# CC-USB-CB.net
KiCad netlist of a schematic drawn in EAGLE
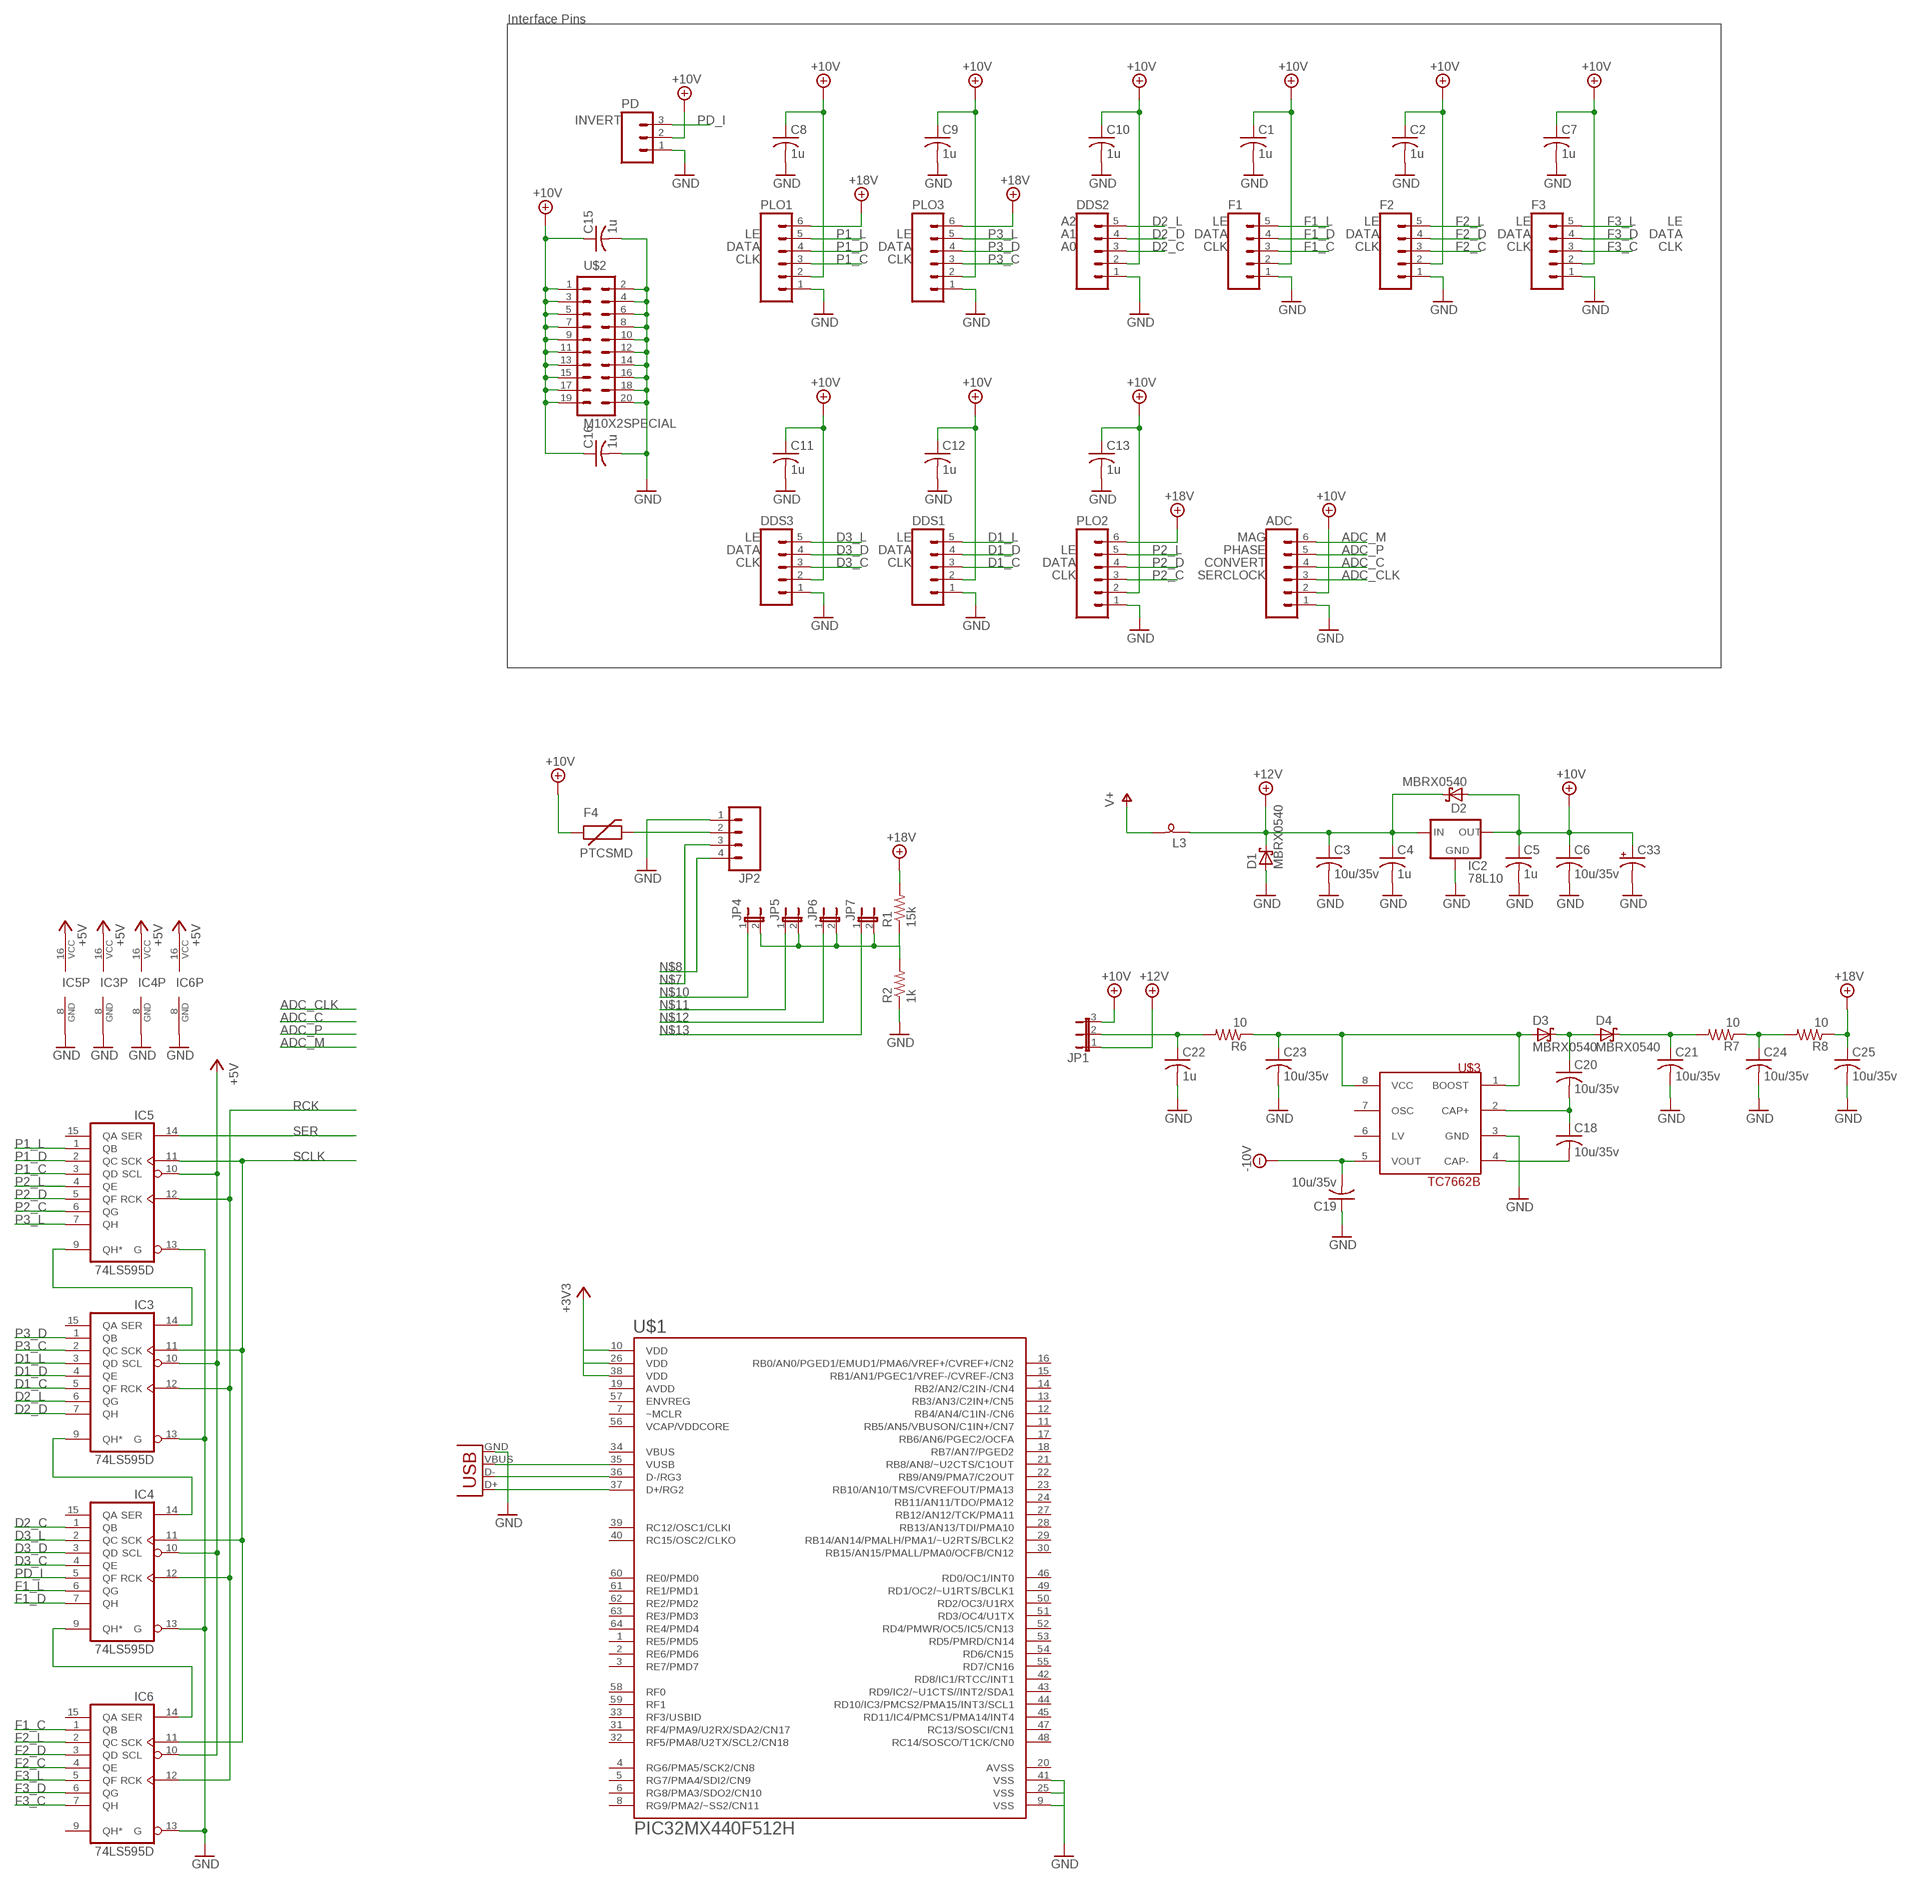
[diagram p0: schematic, sheet 1]

(export (version "E")
  (design (tool "Eeschema 10.0.6"))
  (components
    (comp (ref "ADC")
      (value "M06LOCK")
      (footprint "eagle-import:1X06_LOCK")
      (libsource (lib "eagle-import") (part "M06LOCK"))
    )
    (comp (ref "C1")
      (value "1u")
      (footprint "eagle-import:C0603")
      (libsource (lib "eagle-import") (part "C-USC0603"))
    )
    (comp (ref "C2")
      (value "1u")
      (footprint "eagle-import:C0603")
      (libsource (lib "eagle-import") (part "C-USC0603"))
    )
    (comp (ref "C3")
      (value "10u/35v")
      (footprint "eagle-import:C1206")
      (libsource (lib "eagle-import") (part "C-USC1206"))
    )
    (comp (ref "C4")
      (value "1u")
      (footprint "eagle-import:C0603")
      (libsource (lib "eagle-import") (part "C-USC0603"))
    )
    (comp (ref "C5")
      (value "1u")
      (footprint "eagle-import:C0603")
      (libsource (lib "eagle-import") (part "C-USC0603"))
    )
    (comp (ref "C6")
      (value "10u/35v")
      (footprint "eagle-import:C1206")
      (libsource (lib "eagle-import") (part "C-USC1206"))
    )
    (comp (ref "C7")
      (value "1u")
      (footprint "eagle-import:C0603")
      (libsource (lib "eagle-import") (part "C-USC0603"))
    )
    (comp (ref "C8")
      (value "1u")
      (footprint "eagle-import:C0603")
      (libsource (lib "eagle-import") (part "C-USC0603"))
    )
    (comp (ref "C9")
      (value "1u")
      (footprint "eagle-import:C0603")
      (libsource (lib "eagle-import") (part "C-USC0603"))
    )
    (comp (ref "C10")
      (value "1u")
      (footprint "eagle-import:C0603")
      (libsource (lib "eagle-import") (part "C-USC0603"))
    )
    (comp (ref "C11")
      (value "1u")
      (footprint "eagle-import:C0603")
      (libsource (lib "eagle-import") (part "C-USC0603"))
    )
    (comp (ref "C12")
      (value "1u")
      (footprint "eagle-import:C0603")
      (libsource (lib "eagle-import") (part "C-USC0603"))
    )
    (comp (ref "C13")
      (value "1u")
      (footprint "eagle-import:C0603")
      (libsource (lib "eagle-import") (part "C-USC0603"))
    )
    (comp (ref "C15")
      (value "1u")
      (footprint "eagle-import:C0603")
      (libsource (lib "eagle-import") (part "C-USC0603"))
    )
    (comp (ref "C16")
      (value "1u")
      (footprint "eagle-import:C0603")
      (libsource (lib "eagle-import") (part "C-USC0603"))
    )
    (comp (ref "C18")
      (value "10u/35v")
      (footprint "eagle-import:C1206")
      (libsource (lib "eagle-import") (part "C-USC1206"))
    )
    (comp (ref "C19")
      (value "10u/35v")
      (footprint "eagle-import:C1206")
      (libsource (lib "eagle-import") (part "C-USC1206"))
    )
    (comp (ref "C20")
      (value "10u/35v")
      (footprint "eagle-import:C1206")
      (libsource (lib "eagle-import") (part "C-USC1206"))
    )
    (comp (ref "C21")
      (value "10u/35v")
      (footprint "eagle-import:C1206")
      (libsource (lib "eagle-import") (part "C-USC1206"))
    )
    (comp (ref "C22")
      (value "1u")
      (footprint "eagle-import:C0603")
      (libsource (lib "eagle-import") (part "C-USC0603"))
    )
    (comp (ref "C23")
      (value "10u/35v")
      (footprint "eagle-import:C1206")
      (libsource (lib "eagle-import") (part "C-USC1206"))
    )
    (comp (ref "C24")
      (value "10u/35v")
      (footprint "eagle-import:C1206")
      (libsource (lib "eagle-import") (part "C-USC1206"))
    )
    (comp (ref "C25")
      (value "10u/35v")
      (footprint "eagle-import:C1206")
      (libsource (lib "eagle-import") (part "C-USC1206"))
    )
    (comp (ref "C33")
      (value "CPOL-USE2.5-6")
      (footprint "eagle-import:E2,5-6")
      (libsource (lib "eagle-import") (part "CPOL-USE2.5-6"))
    )
    (comp (ref "D1")
      (value "MBRX0540")
      (footprint "eagle-import:SOD323-R")
      (libsource (lib "eagle-import") (part "MBRX0540"))
    )
    (comp (ref "D2")
      (value "MBRX0540")
      (footprint "eagle-import:SOD323-R")
      (libsource (lib "eagle-import") (part "MBRX0540"))
    )
    (comp (ref "D3")
      (value "MBRX0540")
      (footprint "eagle-import:SOD323-R")
      (libsource (lib "eagle-import") (part "MBRX0540"))
    )
    (comp (ref "D4")
      (value "MBRX0540")
      (footprint "eagle-import:SOD323-R")
      (libsource (lib "eagle-import") (part "MBRX0540"))
    )
    (comp (ref "DDS1")
      (value "M05LOCK")
      (footprint "eagle-import:1X05_LOCK")
      (libsource (lib "eagle-import") (part "M05LOCK"))
    )
    (comp (ref "DDS2")
      (value "M05LOCK")
      (footprint "eagle-import:1X05_LOCK")
      (libsource (lib "eagle-import") (part "M05LOCK"))
    )
    (comp (ref "DDS3")
      (value "M05LOCK")
      (footprint "eagle-import:1X05_LOCK")
      (libsource (lib "eagle-import") (part "M05LOCK"))
    )
    (comp (ref "F1")
      (value "M05LOCK")
      (footprint "eagle-import:1X05_LOCK")
      (libsource (lib "eagle-import") (part "M05LOCK"))
    )
    (comp (ref "F2")
      (value "M05LOCK")
      (footprint "eagle-import:1X05_LOCK")
      (libsource (lib "eagle-import") (part "M05LOCK"))
    )
    (comp (ref "F3")
      (value "M05LOCK")
      (footprint "eagle-import:1X05_LOCK")
      (libsource (lib "eagle-import") (part "M05LOCK"))
    )
    (comp (ref "F4")
      (value "PTCSMD")
      (footprint "eagle-import:PTC-1206")
      (libsource (lib "eagle-import") (part "PTCSMD"))
    )
    (comp (ref "IC2")
      (value "78L10")
      (footprint "eagle-import:78XXS")
      (libsource (lib "eagle-import") (part "78XXS"))
    )
    (comp (ref "IC3")
      (value "74LS595D")
      (footprint "eagle-import:SO16")
      (libsource (lib "eagle-import") (part "74595DLS"))
    )
    (comp (ref "IC4")
      (value "74LS595D")
      (footprint "eagle-import:SO16")
      (libsource (lib "eagle-import") (part "74595DLS"))
    )
    (comp (ref "IC5")
      (value "74LS595D")
      (footprint "eagle-import:SO16")
      (libsource (lib "eagle-import") (part "74595DLS"))
    )
    (comp (ref "IC6")
      (value "74LS595D")
      (footprint "eagle-import:SO16")
      (libsource (lib "eagle-import") (part "74595DLS"))
    )
    (comp (ref "JP1")
      (value "JP2E")
      (footprint "eagle-import:JP2")
      (libsource (lib "eagle-import") (part "JP2E"))
    )
    (comp (ref "JP2")
      (value "M04LOCK")
      (footprint "eagle-import:1X04_LOCK")
      (libsource (lib "eagle-import") (part "M04LOCK"))
    )
    (comp (ref "JP4")
      (value "JUMPER-2SMD-NO")
      (footprint "eagle-import:SJ_2S-NO")
      (libsource (lib "eagle-import") (part "JUMPER-2SMD-NO"))
    )
    (comp (ref "JP5")
      (value "JUMPER-2SMD-NO")
      (footprint "eagle-import:SJ_2S-NO")
      (libsource (lib "eagle-import") (part "JUMPER-2SMD-NO"))
    )
    (comp (ref "JP6")
      (value "JUMPER-2SMD-NO")
      (footprint "eagle-import:SJ_2S-NO")
      (libsource (lib "eagle-import") (part "JUMPER-2SMD-NO"))
    )
    (comp (ref "JP7")
      (value "JUMPER-2SMD-NO")
      (footprint "eagle-import:SJ_2S-NO")
      (libsource (lib "eagle-import") (part "JUMPER-2SMD-NO"))
    )
    (comp (ref "L3")
      (value "SM-B5")
      (footprint "eagle-import:SM-B5")
      (libsource (lib "eagle-import") (part "SM-B5"))
    )
    (comp (ref "PD")
      (value "M03LOCK")
      (footprint "eagle-import:1X03_LOCK")
      (libsource (lib "eagle-import") (part "M03LOCK"))
    )
    (comp (ref "PLO1")
      (value "M06LOCK")
      (footprint "eagle-import:1X06_LOCK")
      (libsource (lib "eagle-import") (part "M06LOCK"))
    )
    (comp (ref "PLO2")
      (value "M06LOCK")
      (footprint "eagle-import:1X06_LOCK")
      (libsource (lib "eagle-import") (part "M06LOCK"))
    )
    (comp (ref "PLO3")
      (value "M06LOCK")
      (footprint "eagle-import:1X06_LOCK")
      (libsource (lib "eagle-import") (part "M06LOCK"))
    )
    (comp (ref "R1")
      (value "15k")
      (footprint "eagle-import:R0603")
      (libsource (lib "eagle-import") (part "R-US_R0603"))
    )
    (comp (ref "R2")
      (value "1k")
      (footprint "eagle-import:R0603")
      (libsource (lib "eagle-import") (part "R-US_R0603"))
    )
    (comp (ref "R6")
      (value "10")
      (footprint "eagle-import:R0603")
      (libsource (lib "eagle-import") (part "R-US_R0603"))
    )
    (comp (ref "R7")
      (value "10")
      (footprint "eagle-import:R0603")
      (libsource (lib "eagle-import") (part "R-US_R0603"))
    )
    (comp (ref "R8")
      (value "10")
      (footprint "eagle-import:R0603")
      (libsource (lib "eagle-import") (part "R-US_R0603"))
    )
    (comp (ref "U$1")
      (value "PIC32MX440F512H")
      (footprint "eagle-import:SQFP-S-10X10-64")
      (libsource (lib "eagle-import") (part "PIC32MX440F512H"))
    )
    (comp (ref "U$2")
      (value "M10X2SPECIAL")
      (footprint "eagle-import:2X10_LOCK_SPECIAL")
      (libsource (lib "eagle-import") (part "M10X2SPECIAL"))
    )
    (comp (ref "U$3")
      (value "TC7662B")
      (footprint "eagle-import:SO-08")
      (libsource (lib "eagle-import") (part "TC7662B"))
    )
    (comp (ref "X1")
      (value "USBPTH-VERTICAL")
      (footprint "eagle-import:USB-B-PTH-VERTICAL")
      (libsource (lib "eagle-import") (part "USBPTH-VERTICAL"))
    )
  )
  (nets
    (net (code "1") (name "+3V3") (class "Default")
      (node (ref "U$1") (pin "10") (pinfunction "VDD_10") (pintype "bidirectional"))
      (node (ref "U$1") (pin "26") (pinfunction "VDD_26") (pintype "bidirectional"))
      (node (ref "U$1") (pin "38") (pinfunction "VDD_38") (pintype "bidirectional"))
    )
    (net (code "2") (name "+5V") (class "Default")
      (node (ref "IC3") (pin "10") (pinfunction "SCL_10") (pintype "input"))
      (node (ref "IC3") (pin "16") (pinfunction "VCC_16") (pintype "power_in"))
      (node (ref "IC4") (pin "10") (pinfunction "SCL_10") (pintype "input"))
      (node (ref "IC4") (pin "16") (pinfunction "VCC_16") (pintype "power_in"))
      (node (ref "IC5") (pin "10") (pinfunction "SCL_10") (pintype "input"))
      (node (ref "IC5") (pin "16") (pinfunction "VCC_16") (pintype "power_in"))
      (node (ref "IC6") (pin "10") (pinfunction "SCL_10") (pintype "input"))
      (node (ref "IC6") (pin "16") (pinfunction "VCC_16") (pintype "power_in"))
    )
    (net (code "3") (name "+10V") (class "Default")
      (node (ref "ADC") (pin "2") (pinfunction "2_2") (pintype "passive"))
      (node (ref "C1") (pin "1") (pinfunction "1_1") (pintype "passive"))
      (node (ref "C10") (pin "1") (pinfunction "1_1") (pintype "passive"))
      (node (ref "C11") (pin "1") (pinfunction "1_1") (pintype "passive"))
      (node (ref "C12") (pin "1") (pinfunction "1_1") (pintype "passive"))
      (node (ref "C13") (pin "1") (pinfunction "1_1") (pintype "passive"))
      (node (ref "C15") (pin "1") (pinfunction "1_1") (pintype "passive"))
      (node (ref "C16") (pin "1") (pinfunction "1_1") (pintype "passive"))
      (node (ref "C2") (pin "1") (pinfunction "1_1") (pintype "passive"))
      (node (ref "C33") (pin "+") (pinfunction "+_+") (pintype "passive"))
      (node (ref "C5") (pin "1") (pinfunction "1_1") (pintype "passive"))
      (node (ref "C6") (pin "1") (pinfunction "1_1") (pintype "passive"))
      (node (ref "C7") (pin "1") (pinfunction "1_1") (pintype "passive"))
      (node (ref "C8") (pin "1") (pinfunction "1_1") (pintype "passive"))
      (node (ref "C9") (pin "1") (pinfunction "1_1") (pintype "passive"))
      (node (ref "D2") (pin "A") (pinfunction "A_A") (pintype "passive"))
      (node (ref "DDS1") (pin "2") (pinfunction "2_2") (pintype "passive"))
      (node (ref "DDS2") (pin "2") (pinfunction "2_2") (pintype "passive"))
      (node (ref "DDS3") (pin "2") (pinfunction "2_2") (pintype "passive"))
      (node (ref "F1") (pin "2") (pinfunction "2_2") (pintype "passive"))
      (node (ref "F2") (pin "2") (pinfunction "2_2") (pintype "passive"))
      (node (ref "F3") (pin "2") (pinfunction "2_2") (pintype "passive"))
      (node (ref "F4") (pin "1") (pinfunction "1_1") (pintype "bidirectional"))
      (node (ref "IC2") (pin "OUT") (pinfunction "OUT_OUT") (pintype "passive"))
      (node (ref "JP1") (pin "3") (pinfunction "3_3") (pintype "passive"))
      (node (ref "PD") (pin "2") (pinfunction "2_2") (pintype "passive"))
      (node (ref "PLO1") (pin "2") (pinfunction "2_2") (pintype "passive"))
      (node (ref "PLO2") (pin "2") (pinfunction "2_2") (pintype "passive"))
      (node (ref "PLO3") (pin "2") (pinfunction "2_2") (pintype "passive"))
      (node (ref "U$2") (pin "1") (pinfunction "1_1") (pintype "passive"))
      (node (ref "U$2") (pin "11") (pinfunction "11_11") (pintype "passive"))
      (node (ref "U$2") (pin "13") (pinfunction "13_13") (pintype "passive"))
      (node (ref "U$2") (pin "15") (pinfunction "15_15") (pintype "passive"))
      (node (ref "U$2") (pin "17") (pinfunction "17_17") (pintype "passive"))
      (node (ref "U$2") (pin "19") (pinfunction "19_19") (pintype "passive"))
      (node (ref "U$2") (pin "3") (pinfunction "3_3") (pintype "passive"))
      (node (ref "U$2") (pin "5") (pinfunction "5_5") (pintype "passive"))
      (node (ref "U$2") (pin "7") (pinfunction "7_7") (pintype "passive"))
      (node (ref "U$2") (pin "9") (pinfunction "9_9") (pintype "passive"))
    )
    (net (code "4") (name "+12V") (class "Default")
      (node (ref "C3") (pin "1") (pinfunction "1_1") (pintype "passive"))
      (node (ref "C4") (pin "1") (pinfunction "1_1") (pintype "passive"))
      (node (ref "D1") (pin "C") (pinfunction "C_C") (pintype "passive"))
      (node (ref "D2") (pin "C") (pinfunction "C_C") (pintype "passive"))
      (node (ref "IC2") (pin "IN") (pinfunction "IN_IN") (pintype "input"))
      (node (ref "JP1") (pin "1") (pinfunction "1_1") (pintype "passive"))
      (node (ref "L3") (pin "1") (pinfunction "1_1") (pintype "passive"))
    )
    (net (code "5") (name "+18V") (class "Default")
      (node (ref "C25") (pin "1") (pinfunction "1_1") (pintype "passive"))
      (node (ref "PLO1") (pin "6") (pinfunction "6_6") (pintype "passive"))
      (node (ref "PLO2") (pin "6") (pinfunction "6_6") (pintype "passive"))
      (node (ref "PLO3") (pin "6") (pinfunction "6_6") (pintype "passive"))
      (node (ref "R1") (pin "2") (pinfunction "2_2") (pintype "passive"))
      (node (ref "R8") (pin "1") (pinfunction "1_1") (pintype "passive"))
    )
    (net (code "6") (name "-10V") (class "Default")
      (node (ref "C19") (pin "2") (pinfunction "2_2") (pintype "passive"))
      (node (ref "U$3") (pin "5") (pinfunction "VOUT_5") (pintype "bidirectional"))
    )
    (net (code "7") (name "/ADC_C") (class "Default")
      (node (ref "ADC") (pin "4") (pinfunction "4_4") (pintype "passive"))
    )
    (net (code "8") (name "/ADC_CLK") (class "Default")
      (node (ref "ADC") (pin "3") (pinfunction "3_3") (pintype "passive"))
    )
    (net (code "9") (name "/ADC_M") (class "Default")
      (node (ref "ADC") (pin "6") (pinfunction "6_6") (pintype "passive"))
    )
    (net (code "10") (name "/ADC_P") (class "Default")
      (node (ref "ADC") (pin "5") (pinfunction "5_5") (pintype "passive"))
    )
    (net (code "11") (name "/D1_C") (class "Default")
      (node (ref "DDS1") (pin "3") (pinfunction "3_3") (pintype "passive"))
      (node (ref "IC3") (pin "5") (pinfunction "QF_5") (pintype "tri_state"))
    )
    (net (code "12") (name "/D1_D") (class "Default")
      (node (ref "DDS1") (pin "4") (pinfunction "4_4") (pintype "passive"))
      (node (ref "IC3") (pin "4") (pinfunction "QE_4") (pintype "tri_state"))
    )
    (net (code "13") (name "/D1_L") (class "Default")
      (node (ref "DDS1") (pin "5") (pinfunction "5_5") (pintype "passive"))
      (node (ref "IC3") (pin "3") (pinfunction "QD_3") (pintype "tri_state"))
    )
    (net (code "14") (name "/D2_C") (class "Default")
      (node (ref "DDS2") (pin "3") (pinfunction "3_3") (pintype "passive"))
      (node (ref "IC4") (pin "1") (pinfunction "QB_1") (pintype "tri_state"))
    )
    (net (code "15") (name "/D2_D") (class "Default")
      (node (ref "DDS2") (pin "4") (pinfunction "4_4") (pintype "passive"))
      (node (ref "IC3") (pin "7") (pinfunction "QH_7") (pintype "tri_state"))
    )
    (net (code "16") (name "/D2_L") (class "Default")
      (node (ref "DDS2") (pin "5") (pinfunction "5_5") (pintype "passive"))
      (node (ref "IC3") (pin "6") (pinfunction "QG_6") (pintype "tri_state"))
    )
    (net (code "17") (name "/D3_C") (class "Default")
      (node (ref "DDS3") (pin "3") (pinfunction "3_3") (pintype "passive"))
      (node (ref "IC4") (pin "4") (pinfunction "QE_4") (pintype "tri_state"))
    )
    (net (code "18") (name "/D3_D") (class "Default")
      (node (ref "DDS3") (pin "4") (pinfunction "4_4") (pintype "passive"))
      (node (ref "IC4") (pin "3") (pinfunction "QD_3") (pintype "tri_state"))
    )
    (net (code "19") (name "/D3_L") (class "Default")
      (node (ref "DDS3") (pin "5") (pinfunction "5_5") (pintype "passive"))
      (node (ref "IC4") (pin "2") (pinfunction "QC_2") (pintype "tri_state"))
    )
    (net (code "20") (name "/F1_C") (class "Default")
      (node (ref "F1") (pin "3") (pinfunction "3_3") (pintype "passive"))
      (node (ref "IC6") (pin "1") (pinfunction "QB_1") (pintype "tri_state"))
    )
    (net (code "21") (name "/F1_D") (class "Default")
      (node (ref "F1") (pin "4") (pinfunction "4_4") (pintype "passive"))
      (node (ref "IC4") (pin "7") (pinfunction "QH_7") (pintype "tri_state"))
    )
    (net (code "22") (name "/F1_L") (class "Default")
      (node (ref "F1") (pin "5") (pinfunction "5_5") (pintype "passive"))
      (node (ref "IC4") (pin "6") (pinfunction "QG_6") (pintype "tri_state"))
    )
    (net (code "23") (name "/F2_C") (class "Default")
      (node (ref "F2") (pin "3") (pinfunction "3_3") (pintype "passive"))
      (node (ref "IC6") (pin "4") (pinfunction "QE_4") (pintype "tri_state"))
    )
    (net (code "24") (name "/F2_D") (class "Default")
      (node (ref "F2") (pin "4") (pinfunction "4_4") (pintype "passive"))
      (node (ref "IC6") (pin "3") (pinfunction "QD_3") (pintype "tri_state"))
    )
    (net (code "25") (name "/F2_L") (class "Default")
      (node (ref "F2") (pin "5") (pinfunction "5_5") (pintype "passive"))
      (node (ref "IC6") (pin "2") (pinfunction "QC_2") (pintype "tri_state"))
    )
    (net (code "26") (name "/F3_C") (class "Default")
      (node (ref "F3") (pin "3") (pinfunction "3_3") (pintype "passive"))
      (node (ref "IC6") (pin "7") (pinfunction "QH_7") (pintype "tri_state"))
    )
    (net (code "27") (name "/F3_D") (class "Default")
      (node (ref "F3") (pin "4") (pinfunction "4_4") (pintype "passive"))
      (node (ref "IC6") (pin "6") (pinfunction "QG_6") (pintype "tri_state"))
    )
    (net (code "28") (name "/F3_L") (class "Default")
      (node (ref "F3") (pin "5") (pinfunction "5_5") (pintype "passive"))
      (node (ref "IC6") (pin "5") (pinfunction "QF_5") (pintype "tri_state"))
    )
    (net (code "29") (name "/N$7") (class "Default")
      (node (ref "JP2") (pin "3") (pinfunction "3_3") (pintype "passive"))
    )
    (net (code "30") (name "/N$8") (class "Default")
      (node (ref "JP2") (pin "4") (pinfunction "4_4") (pintype "passive"))
    )
    (net (code "31") (name "/N$10") (class "Default")
      (node (ref "JP4") (pin "1") (pinfunction "1_1") (pintype "passive"))
    )
    (net (code "32") (name "/N$11") (class "Default")
      (node (ref "JP5") (pin "1") (pinfunction "1_1") (pintype "passive"))
    )
    (net (code "33") (name "/N$12") (class "Default")
      (node (ref "JP6") (pin "1") (pinfunction "1_1") (pintype "passive"))
    )
    (net (code "34") (name "/N$13") (class "Default")
      (node (ref "JP7") (pin "1") (pinfunction "1_1") (pintype "passive"))
    )
    (net (code "35") (name "/P1_C") (class "Default")
      (node (ref "IC5") (pin "3") (pinfunction "QD_3") (pintype "tri_state"))
      (node (ref "PLO1") (pin "3") (pinfunction "3_3") (pintype "passive"))
    )
    (net (code "36") (name "/P1_D") (class "Default")
      (node (ref "IC5") (pin "2") (pinfunction "QC_2") (pintype "tri_state"))
      (node (ref "PLO1") (pin "4") (pinfunction "4_4") (pintype "passive"))
    )
    (net (code "37") (name "/P1_L") (class "Default")
      (node (ref "IC5") (pin "1") (pinfunction "QB_1") (pintype "tri_state"))
      (node (ref "PLO1") (pin "5") (pinfunction "5_5") (pintype "passive"))
    )
    (net (code "38") (name "/P2_C") (class "Default")
      (node (ref "IC5") (pin "6") (pinfunction "QG_6") (pintype "tri_state"))
      (node (ref "PLO2") (pin "3") (pinfunction "3_3") (pintype "passive"))
    )
    (net (code "39") (name "/P2_D") (class "Default")
      (node (ref "IC5") (pin "5") (pinfunction "QF_5") (pintype "tri_state"))
      (node (ref "PLO2") (pin "4") (pinfunction "4_4") (pintype "passive"))
    )
    (net (code "40") (name "/P2_L") (class "Default")
      (node (ref "IC5") (pin "4") (pinfunction "QE_4") (pintype "tri_state"))
      (node (ref "PLO2") (pin "5") (pinfunction "5_5") (pintype "passive"))
    )
    (net (code "41") (name "/P3_C") (class "Default")
      (node (ref "IC3") (pin "2") (pinfunction "QC_2") (pintype "tri_state"))
      (node (ref "PLO3") (pin "3") (pinfunction "3_3") (pintype "passive"))
    )
    (net (code "42") (name "/P3_D") (class "Default")
      (node (ref "IC3") (pin "1") (pinfunction "QB_1") (pintype "tri_state"))
      (node (ref "PLO3") (pin "4") (pinfunction "4_4") (pintype "passive"))
    )
    (net (code "43") (name "/P3_L") (class "Default")
      (node (ref "IC5") (pin "7") (pinfunction "QH_7") (pintype "tri_state"))
      (node (ref "PLO3") (pin "5") (pinfunction "5_5") (pintype "passive"))
    )
    (net (code "44") (name "/PD_I") (class "Default")
      (node (ref "IC4") (pin "5") (pinfunction "QF_5") (pintype "tri_state"))
      (node (ref "PD") (pin "3") (pinfunction "3_3") (pintype "passive"))
    )
    (net (code "45") (name "/RCK") (class "Default")
      (node (ref "IC3") (pin "12") (pinfunction "RCK_12") (pintype "input"))
      (node (ref "IC4") (pin "12") (pinfunction "RCK_12") (pintype "input"))
      (node (ref "IC5") (pin "12") (pinfunction "RCK_12") (pintype "input"))
      (node (ref "IC6") (pin "12") (pinfunction "RCK_12") (pintype "input"))
    )
    (net (code "46") (name "/SCLK") (class "Default")
      (node (ref "IC3") (pin "11") (pinfunction "SCK_11") (pintype "input"))
      (node (ref "IC4") (pin "11") (pinfunction "SCK_11") (pintype "input"))
      (node (ref "IC5") (pin "11") (pinfunction "SCK_11") (pintype "input"))
      (node (ref "IC6") (pin "11") (pinfunction "SCK_11") (pintype "input"))
    )
    (net (code "47") (name "/SER") (class "Default")
      (node (ref "IC5") (pin "14") (pinfunction "SER_14") (pintype "input"))
    )
    (net (code "48") (name "GND") (class "Default")
      (node (ref "ADC") (pin "1") (pinfunction "1_1") (pintype "passive"))
      (node (ref "C1") (pin "2") (pinfunction "2_2") (pintype "passive"))
      (node (ref "C10") (pin "2") (pinfunction "2_2") (pintype "passive"))
      (node (ref "C11") (pin "2") (pinfunction "2_2") (pintype "passive"))
      (node (ref "C12") (pin "2") (pinfunction "2_2") (pintype "passive"))
      (node (ref "C13") (pin "2") (pinfunction "2_2") (pintype "passive"))
      (node (ref "C15") (pin "2") (pinfunction "2_2") (pintype "passive"))
      (node (ref "C16") (pin "2") (pinfunction "2_2") (pintype "passive"))
      (node (ref "C19") (pin "1") (pinfunction "1_1") (pintype "passive"))
      (node (ref "C2") (pin "2") (pinfunction "2_2") (pintype "passive"))
      (node (ref "C21") (pin "2") (pinfunction "2_2") (pintype "passive"))
      (node (ref "C22") (pin "2") (pinfunction "2_2") (pintype "passive"))
      (node (ref "C23") (pin "2") (pinfunction "2_2") (pintype "passive"))
      (node (ref "C24") (pin "2") (pinfunction "2_2") (pintype "passive"))
      (node (ref "C25") (pin "2") (pinfunction "2_2") (pintype "passive"))
      (node (ref "C3") (pin "2") (pinfunction "2_2") (pintype "passive"))
      (node (ref "C33") (pin "-") (pinfunction "-_-") (pintype "passive"))
      (node (ref "C4") (pin "2") (pinfunction "2_2") (pintype "passive"))
      (node (ref "C5") (pin "2") (pinfunction "2_2") (pintype "passive"))
      (node (ref "C6") (pin "2") (pinfunction "2_2") (pintype "passive"))
      (node (ref "C7") (pin "2") (pinfunction "2_2") (pintype "passive"))
      (node (ref "C8") (pin "2") (pinfunction "2_2") (pintype "passive"))
      (node (ref "C9") (pin "2") (pinfunction "2_2") (pintype "passive"))
      (node (ref "D1") (pin "A") (pinfunction "A_A") (pintype "passive"))
      (node (ref "DDS1") (pin "1") (pinfunction "1_1") (pintype "passive"))
      (node (ref "DDS2") (pin "1") (pinfunction "1_1") (pintype "passive"))
      (node (ref "DDS3") (pin "1") (pinfunction "1_1") (pintype "passive"))
      (node (ref "F1") (pin "1") (pinfunction "1_1") (pintype "passive"))
      (node (ref "F2") (pin "1") (pinfunction "1_1") (pintype "passive"))
      (node (ref "F3") (pin "1") (pinfunction "1_1") (pintype "passive"))
      (node (ref "IC2") (pin "GND") (pinfunction "GND_GND") (pintype "input"))
      (node (ref "IC3") (pin "13") (pinfunction "G_13") (pintype "input"))
      (node (ref "IC3") (pin "8") (pinfunction "GND_8") (pintype "power_in"))
      (node (ref "IC4") (pin "13") (pinfunction "G_13") (pintype "input"))
      (node (ref "IC4") (pin "8") (pinfunction "GND_8") (pintype "power_in"))
      (node (ref "IC5") (pin "13") (pinfunction "G_13") (pintype "input"))
      (node (ref "IC5") (pin "8") (pinfunction "GND_8") (pintype "power_in"))
      (node (ref "IC6") (pin "13") (pinfunction "G_13") (pintype "input"))
      (node (ref "IC6") (pin "8") (pinfunction "GND_8") (pintype "power_in"))
      (node (ref "JP2") (pin "1") (pinfunction "1_1") (pintype "passive"))
      (node (ref "PD") (pin "1") (pinfunction "1_1") (pintype "passive"))
      (node (ref "PLO1") (pin "1") (pinfunction "1_1") (pintype "passive"))
      (node (ref "PLO2") (pin "1") (pinfunction "1_1") (pintype "passive"))
      (node (ref "PLO3") (pin "1") (pinfunction "1_1") (pintype "passive"))
      (node (ref "R2") (pin "1") (pinfunction "1_1") (pintype "passive"))
      (node (ref "U$1") (pin "25") (pinfunction "VSS_25") (pintype "bidirectional"))
      (node (ref "U$1") (pin "41") (pinfunction "VSS_41") (pintype "bidirectional"))
      (node (ref "U$1") (pin "9") (pinfunction "VSS_9") (pintype "bidirectional"))
      (node (ref "U$2") (pin "10") (pinfunction "10_10") (pintype "passive"))
      (node (ref "U$2") (pin "12") (pinfunction "12_12") (pintype "passive"))
      (node (ref "U$2") (pin "14") (pinfunction "14_14") (pintype "passive"))
      (node (ref "U$2") (pin "16") (pinfunction "16_16") (pintype "passive"))
      (node (ref "U$2") (pin "18") (pinfunction "18_18") (pintype "passive"))
      (node (ref "U$2") (pin "2") (pinfunction "2_2") (pintype "passive"))
      (node (ref "U$2") (pin "20") (pinfunction "20_20") (pintype "passive"))
      (node (ref "U$2") (pin "4") (pinfunction "4_4") (pintype "passive"))
      (node (ref "U$2") (pin "6") (pinfunction "6_6") (pintype "passive"))
      (node (ref "U$2") (pin "8") (pinfunction "8_8") (pintype "passive"))
      (node (ref "U$3") (pin "3") (pinfunction "GND_3") (pintype "bidirectional"))
      (node (ref "X1") (pin "GND") (pinfunction "GND_GND") (pintype "bidirectional"))
    )
    (net (code "49") (name "Net-(C20-Pad1)") (class "Default")
      (node (ref "C20") (pin "1") (pinfunction "1_1") (pintype "passive"))
      (node (ref "D3") (pin "C") (pinfunction "C_C") (pintype "passive"))
      (node (ref "D4") (pin "A") (pinfunction "A_A") (pintype "passive"))
    )
    (net (code "50") (name "Net-(C21-Pad1)") (class "Default")
      (node (ref "C21") (pin "1") (pinfunction "1_1") (pintype "passive"))
      (node (ref "D4") (pin "C") (pinfunction "C_C") (pintype "passive"))
      (node (ref "R7") (pin "2") (pinfunction "2_2") (pintype "passive"))
    )
    (net (code "51") (name "Net-(C22-Pad1)") (class "Default")
      (node (ref "C22") (pin "1") (pinfunction "1_1") (pintype "passive"))
      (node (ref "JP1") (pin "2") (pinfunction "2_2") (pintype "passive"))
      (node (ref "R6") (pin "2") (pinfunction "2_2") (pintype "passive"))
    )
    (net (code "52") (name "Net-(C24-Pad1)") (class "Default")
      (node (ref "C24") (pin "1") (pinfunction "1_1") (pintype "passive"))
      (node (ref "R7") (pin "1") (pinfunction "1_1") (pintype "passive"))
      (node (ref "R8") (pin "2") (pinfunction "2_2") (pintype "passive"))
    )
    (net (code "53") (name "Net-(F4-Pad2)") (class "Default")
      (node (ref "F4") (pin "2") (pinfunction "2_2") (pintype "bidirectional"))
      (node (ref "JP2") (pin "2") (pinfunction "2_2") (pintype "passive"))
    )
    (net (code "54") (name "Net-(IC3A-QH*)") (class "Default")
      (node (ref "IC3") (pin "9") (pinfunction "QH*_9") (pintype "tri_state"))
      (node (ref "IC4") (pin "14") (pinfunction "SER_14") (pintype "input"))
    )
    (net (code "55") (name "Net-(IC3A-SER)") (class "Default")
      (node (ref "IC3") (pin "14") (pinfunction "SER_14") (pintype "input"))
      (node (ref "IC5") (pin "9") (pinfunction "QH*_9") (pintype "tri_state"))
    )
    (net (code "56") (name "Net-(IC4A-QH*)") (class "Default")
      (node (ref "IC4") (pin "9") (pinfunction "QH*_9") (pintype "tri_state"))
      (node (ref "IC6") (pin "14") (pinfunction "SER_14") (pintype "input"))
    )
    (net (code "57") (name "Net-(JP4-Pad2)") (class "Default")
      (node (ref "JP4") (pin "2") (pinfunction "2_2") (pintype "passive"))
      (node (ref "JP5") (pin "2") (pinfunction "2_2") (pintype "passive"))
      (node (ref "JP6") (pin "2") (pinfunction "2_2") (pintype "passive"))
      (node (ref "JP7") (pin "2") (pinfunction "2_2") (pintype "passive"))
      (node (ref "R1") (pin "1") (pinfunction "1_1") (pintype "passive"))
      (node (ref "R2") (pin "2") (pinfunction "2_2") (pintype "passive"))
    )
    (net (code "58") (name "Net-(U$1-D+{slash}RG2)") (class "Default")
      (node (ref "U$1") (pin "37") (pinfunction "D+/RG2_37") (pintype "bidirectional"))
      (node (ref "X1") (pin "D+") (pinfunction "D+_D+") (pintype "bidirectional"))
    )
    (net (code "59") (name "Net-(U$1-D-{slash}RG3)") (class "Default")
      (node (ref "U$1") (pin "36") (pinfunction "D-/RG3_36") (pintype "bidirectional"))
      (node (ref "X1") (pin "D-") (pinfunction "D-_D-") (pintype "bidirectional"))
    )
    (net (code "60") (name "Net-(U$1-VUSB)") (class "Default")
      (node (ref "U$1") (pin "35") (pinfunction "VUSB_35") (pintype "bidirectional"))
      (node (ref "X1") (pin "VBUS") (pinfunction "VBUS_VBUS") (pintype "bidirectional"))
    )
    (net (code "61") (name "Net-(U$3-BOOST)") (class "Default")
      (node (ref "C23") (pin "1") (pinfunction "1_1") (pintype "passive"))
      (node (ref "D3") (pin "A") (pinfunction "A_A") (pintype "passive"))
      (node (ref "R6") (pin "1") (pinfunction "1_1") (pintype "passive"))
      (node (ref "U$3") (pin "1") (pinfunction "BOOST_1") (pintype "bidirectional"))
      (node (ref "U$3") (pin "8") (pinfunction "VCC_8") (pintype "bidirectional"))
    )
    (net (code "62") (name "Net-(U$3-CAP+)") (class "Default")
      (node (ref "C18") (pin "1") (pinfunction "1_1") (pintype "passive"))
      (node (ref "C20") (pin "2") (pinfunction "2_2") (pintype "passive"))
      (node (ref "U$3") (pin "2") (pinfunction "CAP+_2") (pintype "bidirectional"))
    )
    (net (code "63") (name "Net-(U$3-CAP-)") (class "Default")
      (node (ref "C18") (pin "2") (pinfunction "2_2") (pintype "passive"))
      (node (ref "U$3") (pin "4") (pinfunction "CAP-_4") (pintype "bidirectional"))
    )
    (net (code "64") (name "V+") (class "Default")
      (node (ref "L3") (pin "2") (pinfunction "2_2") (pintype "passive"))
    )
    (net (code "65") (name "unconnected-(IC3A-QA-Pad15)") (class "Default")
      (node (ref "IC3") (pin "15") (pinfunction "QA_15") (pintype "tri_state"))
    )
    (net (code "66") (name "unconnected-(IC4A-QA-Pad15)") (class "Default")
      (node (ref "IC4") (pin "15") (pinfunction "QA_15") (pintype "tri_state"))
    )
    (net (code "67") (name "unconnected-(IC5A-QA-Pad15)") (class "Default")
      (node (ref "IC5") (pin "15") (pinfunction "QA_15") (pintype "tri_state"))
    )
    (net (code "68") (name "unconnected-(IC6A-QA-Pad15)") (class "Default")
      (node (ref "IC6") (pin "15") (pinfunction "QA_15") (pintype "tri_state"))
    )
    (net (code "69") (name "unconnected-(IC6A-QH*-Pad9)") (class "Default")
      (node (ref "IC6") (pin "9") (pinfunction "QH*_9") (pintype "tri_state"))
    )
    (net (code "70") (name "unconnected-(U$1-AVDD-Pad19)") (class "Default")
      (node (ref "U$1") (pin "19") (pinfunction "AVDD_19") (pintype "bidirectional"))
    )
    (net (code "71") (name "unconnected-(U$1-AVSS-Pad20)") (class "Default")
      (node (ref "U$1") (pin "20") (pinfunction "AVSS_20") (pintype "bidirectional"))
    )
    (net (code "72") (name "unconnected-(U$1-ENVREG-Pad57)") (class "Default")
      (node (ref "U$1") (pin "57") (pinfunction "ENVREG_57") (pintype "bidirectional"))
    )
    (net (code "73") (name "unconnected-(U$1-RB0{slash}AN0{slash}PGED1{slash}EMUD1{slash}PMA6{slash}VREF+{slash}CVREF+{slash}CN2-Pad16)") (class "Default")
      (node (ref "U$1") (pin "16") (pinfunction "RB0/AN0/PGED1/EMUD1/PMA6/VREF+/CVREF+/CN2_16") (pintype "bidirectional"))
    )
    (net (code "74") (name "unconnected-(U$1-RB1{slash}AN1{slash}PGEC1{slash}VREF-{slash}CVREF-{slash}CN3-Pad15)") (class "Default")
      (node (ref "U$1") (pin "15") (pinfunction "RB1/AN1/PGEC1/VREF-/CVREF-/CN3_15") (pintype "bidirectional"))
    )
    (net (code "75") (name "unconnected-(U$1-RB2{slash}AN2{slash}C2IN-{slash}CN4-Pad14)") (class "Default")
      (node (ref "U$1") (pin "14") (pinfunction "RB2/AN2/C2IN-/CN4_14") (pintype "bidirectional"))
    )
    (net (code "76") (name "unconnected-(U$1-RB3{slash}AN3{slash}C2IN+{slash}CN5-Pad13)") (class "Default")
      (node (ref "U$1") (pin "13") (pinfunction "RB3/AN3/C2IN+/CN5_13") (pintype "bidirectional"))
    )
    (net (code "77") (name "unconnected-(U$1-RB4{slash}AN4{slash}C1IN-{slash}CN6-Pad12)") (class "Default")
      (node (ref "U$1") (pin "12") (pinfunction "RB4/AN4/C1IN-/CN6_12") (pintype "bidirectional"))
    )
    (net (code "78") (name "unconnected-(U$1-RB5{slash}AN5{slash}VBUSON{slash}C1IN+{slash}CN7-Pad11)") (class "Default")
      (node (ref "U$1") (pin "11") (pinfunction "RB5/AN5/VBUSON/C1IN+/CN7_11") (pintype "bidirectional"))
    )
    (net (code "79") (name "unconnected-(U$1-RB6{slash}AN6{slash}PGEC2{slash}OCFA-Pad17)") (class "Default")
      (node (ref "U$1") (pin "17") (pinfunction "RB6/AN6/PGEC2/OCFA_17") (pintype "bidirectional"))
    )
    (net (code "80") (name "unconnected-(U$1-RB7{slash}AN7{slash}PGED2-Pad18)") (class "Default")
      (node (ref "U$1") (pin "18") (pinfunction "RB7/AN7/PGED2_18") (pintype "bidirectional"))
    )
    (net (code "81") (name "unconnected-(U$1-RB8{slash}AN8{slash}~{U2CTS{slash}C1OUT}-Pad21)") (class "Default")
      (node (ref "U$1") (pin "21") (pinfunction "RB8/AN8/~{U2CTS/C1OUT}_21") (pintype "bidirectional"))
    )
    (net (code "82") (name "unconnected-(U$1-RB9{slash}AN9{slash}PMA7{slash}C2OUT-Pad22)") (class "Default")
      (node (ref "U$1") (pin "22") (pinfunction "RB9/AN9/PMA7/C2OUT_22") (pintype "bidirectional"))
    )
    (net (code "83") (name "unconnected-(U$1-RB10{slash}AN10{slash}TMS{slash}CVREFOUT{slash}PMA13-Pad23)") (class "Default")
      (node (ref "U$1") (pin "23") (pinfunction "RB10/AN10/TMS/CVREFOUT/PMA13_23") (pintype "bidirectional"))
    )
    (net (code "84") (name "unconnected-(U$1-RB11{slash}AN11{slash}TDO{slash}PMA12-Pad24)") (class "Default")
      (node (ref "U$1") (pin "24") (pinfunction "RB11/AN11/TDO/PMA12_24") (pintype "bidirectional"))
    )
    (net (code "85") (name "unconnected-(U$1-RB12{slash}AN12{slash}TCK{slash}PMA11-Pad27)") (class "Default")
      (node (ref "U$1") (pin "27") (pinfunction "RB12/AN12/TCK/PMA11_27") (pintype "bidirectional"))
    )
    (net (code "86") (name "unconnected-(U$1-RB13{slash}AN13{slash}TDI{slash}PMA10-Pad28)") (class "Default")
      (node (ref "U$1") (pin "28") (pinfunction "RB13/AN13/TDI/PMA10_28") (pintype "bidirectional"))
    )
    (net (code "87") (name "unconnected-(U$1-RB14{slash}AN14{slash}PMALH{slash}PMA1{slash}~{U2RTS{slash}BCLK2}-Pad29)") (class "Default")
      (node (ref "U$1") (pin "29") (pinfunction "RB14/AN14/PMALH/PMA1/~{U2RTS/BCLK2}_29") (pintype "bidirectional"))
    )
    (net (code "88") (name "unconnected-(U$1-RB15{slash}AN15{slash}PMALL{slash}PMA0{slash}OCFB{slash}CN12-Pad30)") (class "Default")
      (node (ref "U$1") (pin "30") (pinfunction "RB15/AN15/PMALL/PMA0/OCFB/CN12_30") (pintype "bidirectional"))
    )
    (net (code "89") (name "unconnected-(U$1-RC12{slash}OSC1{slash}CLKI-Pad39)") (class "Default")
      (node (ref "U$1") (pin "39") (pinfunction "RC12/OSC1/CLKI_39") (pintype "bidirectional"))
    )
    (net (code "90") (name "unconnected-(U$1-RC13{slash}SOSCI{slash}CN1-Pad47)") (class "Default")
      (node (ref "U$1") (pin "47") (pinfunction "RC13/SOSCI/CN1_47") (pintype "bidirectional"))
    )
    (net (code "91") (name "unconnected-(U$1-RC14{slash}SOSCO{slash}T1CK{slash}CN0-Pad48)") (class "Default")
      (node (ref "U$1") (pin "48") (pinfunction "RC14/SOSCO/T1CK/CN0_48") (pintype "bidirectional"))
    )
    (net (code "92") (name "unconnected-(U$1-RC15{slash}OSC2{slash}CLKO-Pad40)") (class "Default")
      (node (ref "U$1") (pin "40") (pinfunction "RC15/OSC2/CLKO_40") (pintype "bidirectional"))
    )
    (net (code "93") (name "unconnected-(U$1-RD0{slash}OC1{slash}INT0-Pad46)") (class "Default")
      (node (ref "U$1") (pin "46") (pinfunction "RD0/OC1/INT0_46") (pintype "bidirectional"))
    )
    (net (code "94") (name "unconnected-(U$1-RD1{slash}OC2{slash}~{U1RTS{slash}BCLK1}-Pad49)") (class "Default")
      (node (ref "U$1") (pin "49") (pinfunction "RD1/OC2/~{U1RTS/BCLK1}_49") (pintype "bidirectional"))
    )
    (net (code "95") (name "unconnected-(U$1-RD2{slash}OC3{slash}U1RX-Pad50)") (class "Default")
      (node (ref "U$1") (pin "50") (pinfunction "RD2/OC3/U1RX_50") (pintype "bidirectional"))
    )
    (net (code "96") (name "unconnected-(U$1-RD3{slash}OC4{slash}U1TX-Pad51)") (class "Default")
      (node (ref "U$1") (pin "51") (pinfunction "RD3/OC4/U1TX_51") (pintype "bidirectional"))
    )
    (net (code "97") (name "unconnected-(U$1-RD4{slash}PMWR{slash}OC5{slash}IC5{slash}CN13-Pad52)") (class "Default")
      (node (ref "U$1") (pin "52") (pinfunction "RD4/PMWR/OC5/IC5/CN13_52") (pintype "bidirectional"))
    )
    (net (code "98") (name "unconnected-(U$1-RD5{slash}PMRD{slash}CN14-Pad53)") (class "Default")
      (node (ref "U$1") (pin "53") (pinfunction "RD5/PMRD/CN14_53") (pintype "bidirectional"))
    )
    (net (code "99") (name "unconnected-(U$1-RD6{slash}CN15-Pad54)") (class "Default")
      (node (ref "U$1") (pin "54") (pinfunction "RD6/CN15_54") (pintype "bidirectional"))
    )
    (net (code "100") (name "unconnected-(U$1-RD7{slash}CN16-Pad55)") (class "Default")
      (node (ref "U$1") (pin "55") (pinfunction "RD7/CN16_55") (pintype "bidirectional"))
    )
    (net (code "101") (name "unconnected-(U$1-RD8{slash}IC1{slash}RTCC{slash}INT1-Pad42)") (class "Default")
      (node (ref "U$1") (pin "42") (pinfunction "RD8/IC1/RTCC/INT1_42") (pintype "bidirectional"))
    )
    (net (code "102") (name "unconnected-(U$1-RD9{slash}IC2{slash}~{U1CTS{slash}{slash}INT2{slash}SDA1}-Pad43)") (class "Default")
      (node (ref "U$1") (pin "43") (pinfunction "RD9/IC2/~{U1CTS//INT2/SDA1}_43") (pintype "bidirectional"))
    )
    (net (code "103") (name "unconnected-(U$1-RD10{slash}IC3{slash}PMCS2{slash}PMA15{slash}INT3{slash}SCL1-Pad44)") (class "Default")
      (node (ref "U$1") (pin "44") (pinfunction "RD10/IC3/PMCS2/PMA15/INT3/SCL1_44") (pintype "bidirectional"))
    )
    (net (code "104") (name "unconnected-(U$1-RD11{slash}IC4{slash}PMCS1{slash}PMA14{slash}INT4-Pad45)") (class "Default")
      (node (ref "U$1") (pin "45") (pinfunction "RD11/IC4/PMCS1/PMA14/INT4_45") (pintype "bidirectional"))
    )
    (net (code "105") (name "unconnected-(U$1-RE0{slash}PMD0-Pad60)") (class "Default")
      (node (ref "U$1") (pin "60") (pinfunction "RE0/PMD0_60") (pintype "bidirectional"))
    )
    (net (code "106") (name "unconnected-(U$1-RE1{slash}PMD1-Pad61)") (class "Default")
      (node (ref "U$1") (pin "61") (pinfunction "RE1/PMD1_61") (pintype "bidirectional"))
    )
    (net (code "107") (name "unconnected-(U$1-RE2{slash}PMD2-Pad62)") (class "Default")
      (node (ref "U$1") (pin "62") (pinfunction "RE2/PMD2_62") (pintype "bidirectional"))
    )
    (net (code "108") (name "unconnected-(U$1-RE3{slash}PMD3-Pad63)") (class "Default")
      (node (ref "U$1") (pin "63") (pinfunction "RE3/PMD3_63") (pintype "bidirectional"))
    )
    (net (code "109") (name "unconnected-(U$1-RE4{slash}PMD4-Pad64)") (class "Default")
      (node (ref "U$1") (pin "64") (pinfunction "RE4/PMD4_64") (pintype "bidirectional"))
    )
    (net (code "110") (name "unconnected-(U$1-RE5{slash}PMD5-Pad1)") (class "Default")
      (node (ref "U$1") (pin "1") (pinfunction "RE5/PMD5_1") (pintype "bidirectional"))
    )
    (net (code "111") (name "unconnected-(U$1-RE6{slash}PMD6-Pad2)") (class "Default")
      (node (ref "U$1") (pin "2") (pinfunction "RE6/PMD6_2") (pintype "bidirectional"))
    )
    (net (code "112") (name "unconnected-(U$1-RE7{slash}PMD7-Pad3)") (class "Default")
      (node (ref "U$1") (pin "3") (pinfunction "RE7/PMD7_3") (pintype "bidirectional"))
    )
    (net (code "113") (name "unconnected-(U$1-RF0-Pad58)") (class "Default")
      (node (ref "U$1") (pin "58") (pinfunction "RF0_58") (pintype "bidirectional"))
    )
    (net (code "114") (name "unconnected-(U$1-RF1-Pad59)") (class "Default")
      (node (ref "U$1") (pin "59") (pinfunction "RF1_59") (pintype "bidirectional"))
    )
    (net (code "115") (name "unconnected-(U$1-RF3{slash}USBID-Pad33)") (class "Default")
      (node (ref "U$1") (pin "33") (pinfunction "RF3/USBID_33") (pintype "bidirectional"))
    )
    (net (code "116") (name "unconnected-(U$1-RF4{slash}PMA9{slash}U2RX{slash}SDA2{slash}CN17-Pad31)") (class "Default")
      (node (ref "U$1") (pin "31") (pinfunction "RF4/PMA9/U2RX/SDA2/CN17_31") (pintype "bidirectional"))
    )
    (net (code "117") (name "unconnected-(U$1-RF5{slash}PMA8{slash}U2TX{slash}SCL2{slash}CN18-Pad32)") (class "Default")
      (node (ref "U$1") (pin "32") (pinfunction "RF5/PMA8/U2TX/SCL2/CN18_32") (pintype "bidirectional"))
    )
    (net (code "118") (name "unconnected-(U$1-RG6{slash}PMA5{slash}SCK2{slash}CN8-Pad4)") (class "Default")
      (node (ref "U$1") (pin "4") (pinfunction "RG6/PMA5/SCK2/CN8_4") (pintype "bidirectional"))
    )
    (net (code "119") (name "unconnected-(U$1-RG7{slash}PMA4{slash}SDI2{slash}CN9-Pad5)") (class "Default")
      (node (ref "U$1") (pin "5") (pinfunction "RG7/PMA4/SDI2/CN9_5") (pintype "bidirectional"))
    )
    (net (code "120") (name "unconnected-(U$1-RG8{slash}PMA3{slash}SDO2{slash}CN10-Pad6)") (class "Default")
      (node (ref "U$1") (pin "6") (pinfunction "RG8/PMA3/SDO2/CN10_6") (pintype "bidirectional"))
    )
    (net (code "121") (name "unconnected-(U$1-RG9{slash}PMA2{slash}~{SS2{slash}CN11}-Pad8)") (class "Default")
      (node (ref "U$1") (pin "8") (pinfunction "RG9/PMA2/~{SS2/CN11}_8") (pintype "bidirectional"))
    )
    (net (code "122") (name "unconnected-(U$1-VBUS-Pad34)") (class "Default")
      (node (ref "U$1") (pin "34") (pinfunction "VBUS_34") (pintype "bidirectional"))
    )
    (net (code "123") (name "unconnected-(U$1-VCAP{slash}VDDCORE-Pad56)") (class "Default")
      (node (ref "U$1") (pin "56") (pinfunction "VCAP/VDDCORE_56") (pintype "bidirectional"))
    )
    (net (code "124") (name "unconnected-(U$1-~{MCLR}-Pad7)") (class "Default")
      (node (ref "U$1") (pin "7") (pinfunction "~{MCLR}_7") (pintype "bidirectional"))
    )
    (net (code "125") (name "unconnected-(U$3-LV-Pad6)") (class "Default")
      (node (ref "U$3") (pin "6") (pinfunction "LV_6") (pintype "bidirectional"))
    )
    (net (code "126") (name "unconnected-(U$3-OSC-Pad7)") (class "Default")
      (node (ref "U$3") (pin "7") (pinfunction "OSC_7") (pintype "bidirectional"))
    )
  )
)
